# HSPROTO.net
KiCad netlist of a schematic drawn in EAGLE
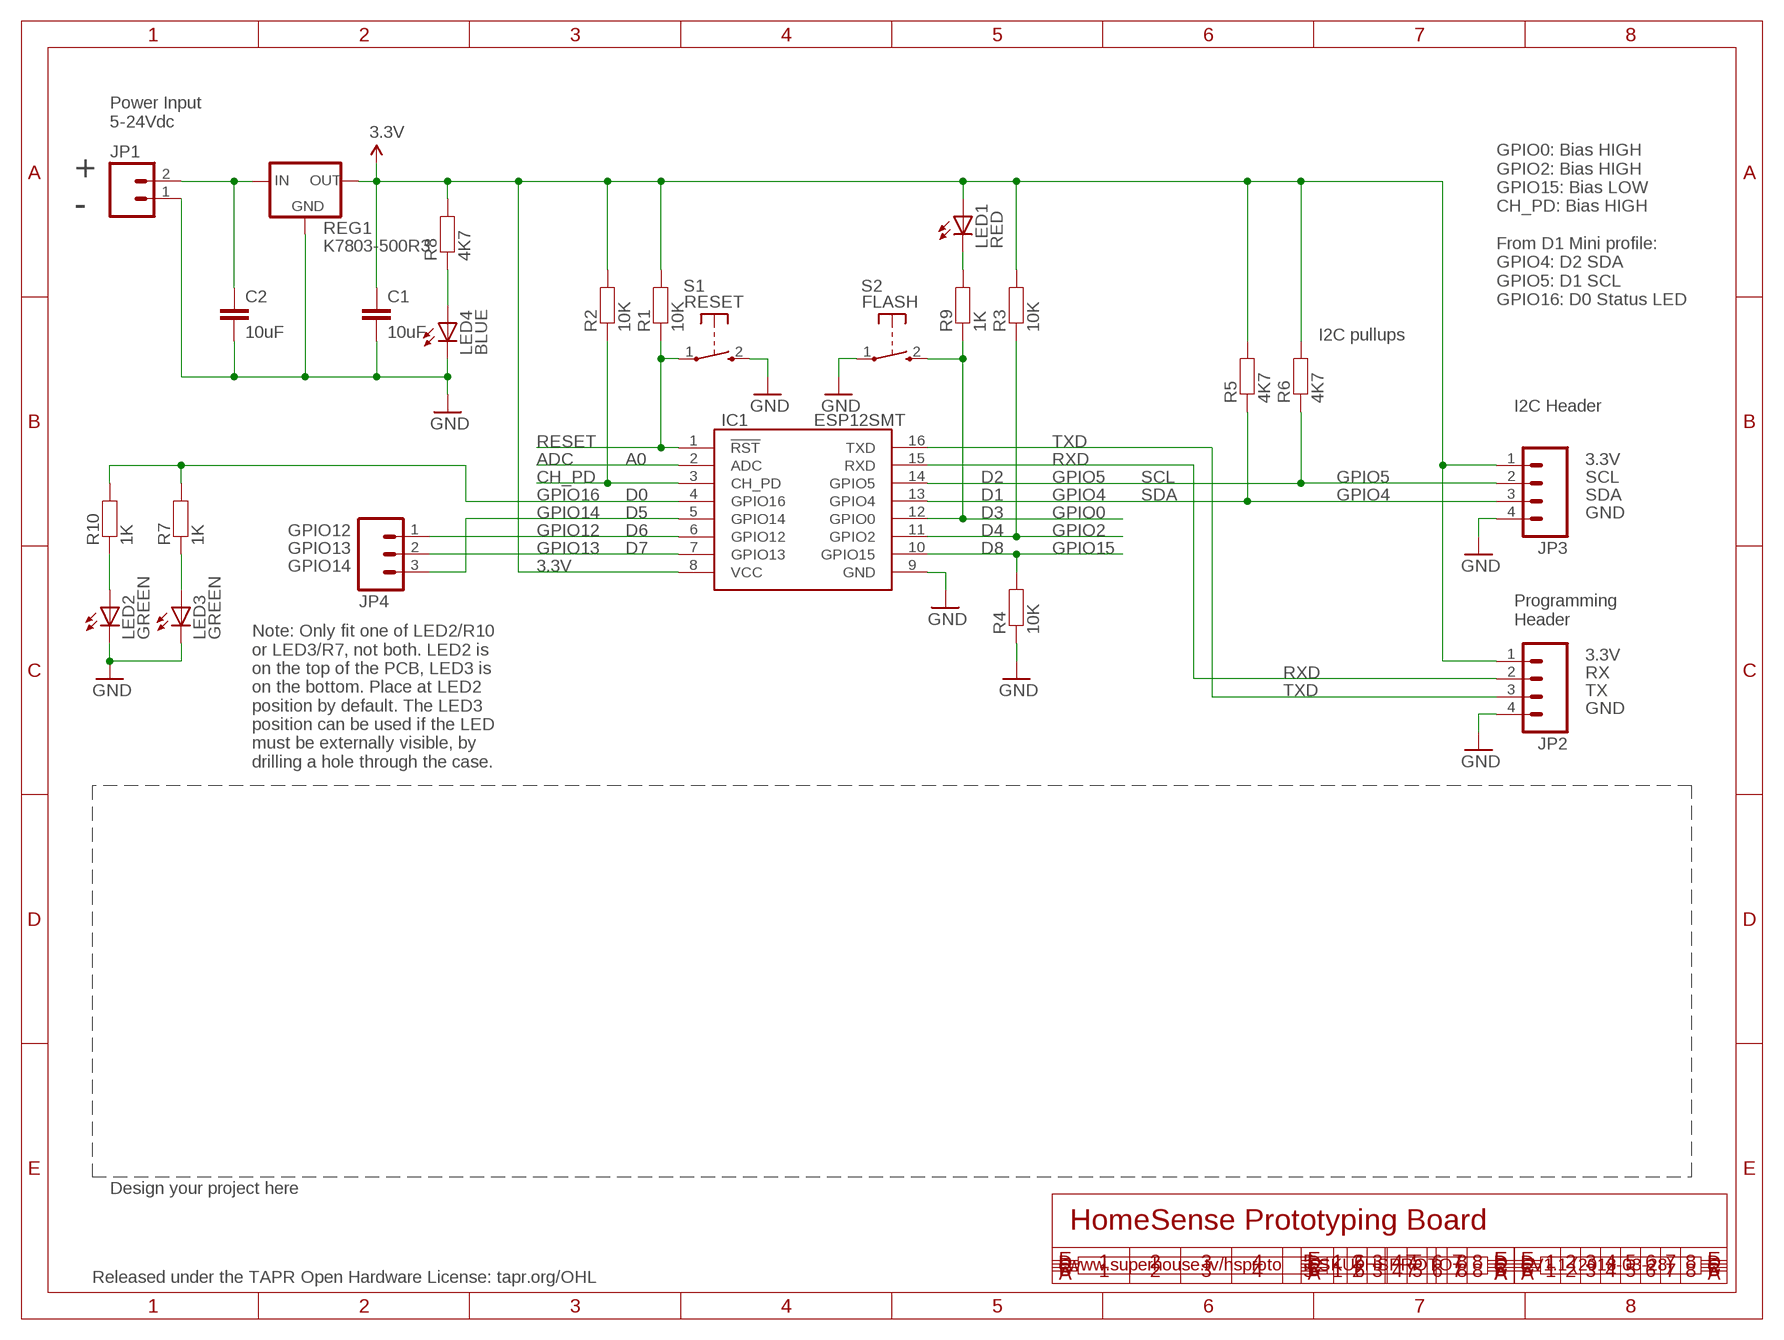
[diagram p0: schematic, sheet 1]

(export (version "E")
  (design (tool "Eeschema 10.0.6"))
  (components
    (comp (ref "C1")
      (value "10uF")
      (footprint "eagle-import:0805")
      (libsource (lib "eagle-import") (part "CAP0805"))
    )
    (comp (ref "C2")
      (value "10uF")
      (footprint "eagle-import:0805")
      (libsource (lib "eagle-import") (part "CAP0805"))
    )
    (comp (ref "IC1")
      (value "ESP12SMT")
      (footprint "eagle-import:ESP12")
      (libsource (lib "eagle-import") (part "ESP12SMT"))
    )
    (comp (ref "JP1")
      (value "M02PTH")
      (footprint "eagle-import:1X02")
      (libsource (lib "eagle-import") (part "M02PTH"))
    )
    (comp (ref "JP2")
      (value "M04PTH")
      (footprint "eagle-import:1X04")
      (libsource (lib "eagle-import") (part "M04PTH"))
    )
    (comp (ref "JP3")
      (value "M04PTH")
      (footprint "eagle-import:1X04")
      (libsource (lib "eagle-import") (part "M04PTH"))
    )
    (comp (ref "JP4")
      (value "M03PTH")
      (footprint "eagle-import:1X03")
      (libsource (lib "eagle-import") (part "M03PTH"))
    )
    (comp (ref "LED1")
      (value "RED")
      (footprint "eagle-import:LED-0603")
      (libsource (lib "eagle-import") (part "LED0603"))
    )
    (comp (ref "LED2")
      (value "GREEN")
      (footprint "eagle-import:LED-0603")
      (libsource (lib "eagle-import") (part "LED0603"))
    )
    (comp (ref "LED3")
      (value "GREEN")
      (footprint "eagle-import:LED-0603")
      (libsource (lib "eagle-import") (part "LED0603"))
    )
    (comp (ref "LED4")
      (value "BLUE")
      (footprint "eagle-import:LED-0603")
      (libsource (lib "eagle-import") (part "LED0603"))
    )
    (comp (ref "R1")
      (value "10K")
      (footprint "eagle-import:0603")
      (libsource (lib "eagle-import") (part "RESISTOR0603"))
    )
    (comp (ref "R2")
      (value "10K")
      (footprint "eagle-import:0603")
      (libsource (lib "eagle-import") (part "RESISTOR0603"))
    )
    (comp (ref "R3")
      (value "10K")
      (footprint "eagle-import:0603")
      (libsource (lib "eagle-import") (part "RESISTOR0603"))
    )
    (comp (ref "R4")
      (value "10K")
      (footprint "eagle-import:0603")
      (libsource (lib "eagle-import") (part "RESISTOR0603"))
    )
    (comp (ref "R5")
      (value "4K7")
      (footprint "eagle-import:0603")
      (libsource (lib "eagle-import") (part "RESISTOR0603"))
    )
    (comp (ref "R6")
      (value "4K7")
      (footprint "eagle-import:0603")
      (libsource (lib "eagle-import") (part "RESISTOR0603"))
    )
    (comp (ref "R7")
      (value "1K")
      (footprint "eagle-import:0603")
      (libsource (lib "eagle-import") (part "RESISTOR0603"))
    )
    (comp (ref "R8")
      (value "4K7")
      (footprint "eagle-import:0603")
      (libsource (lib "eagle-import") (part "RESISTOR0603"))
    )
    (comp (ref "R9")
      (value "1K")
      (footprint "eagle-import:0603")
      (libsource (lib "eagle-import") (part "RESISTOR0603"))
    )
    (comp (ref "R10")
      (value "1K")
      (footprint "eagle-import:0603")
      (libsource (lib "eagle-import") (part "RESISTOR0603"))
    )
    (comp (ref "REG1")
      (value "K7803-500R3")
      (footprint "eagle-import:K78XX-500R3")
      (libsource (lib "eagle-import") (part "K78XX-500R3"))
    )
    (comp (ref "S1")
      (value "RESET")
      (footprint "eagle-import:TACTILE_SWITCH_SMD_2PIN_TINY")
      (libsource (lib "eagle-import") (part "TAC_SWITCH_2PINSMT"))
    )
    (comp (ref "S2")
      (value "FLASH")
      (footprint "eagle-import:TACTILE_SWITCH_SMD_2PIN_TINY")
      (libsource (lib "eagle-import") (part "TAC_SWITCH_2PINSMT"))
    )
  )
  (nets
    (net (code "1") (name "/ADC") (class "Default")
      (node (ref "IC1") (pin "2") (pinfunction "ADC_2") (pintype "input"))
    )
    (net (code "2") (name "/CH_PD") (class "Default")
      (node (ref "IC1") (pin "3") (pinfunction "CH_PD_3") (pintype "input"))
      (node (ref "R2") (pin "1") (pinfunction "1_1") (pintype "passive"))
    )
    (net (code "3") (name "/GPIO0") (class "Default")
      (node (ref "IC1") (pin "12") (pinfunction "GPIO0_12") (pintype "bidirectional"))
      (node (ref "R9") (pin "1") (pinfunction "1_1") (pintype "passive"))
      (node (ref "S2") (pin "2") (pinfunction "S_2") (pintype "passive"))
    )
    (net (code "4") (name "/GPIO2") (class "Default")
      (node (ref "IC1") (pin "11") (pinfunction "GPIO2_11") (pintype "bidirectional"))
      (node (ref "R3") (pin "1") (pinfunction "1_1") (pintype "passive"))
    )
    (net (code "5") (name "/GPIO4") (class "Default")
      (node (ref "IC1") (pin "13") (pinfunction "GPIO4_13") (pintype "bidirectional"))
      (node (ref "JP3") (pin "3") (pinfunction "3_3") (pintype "passive"))
      (node (ref "R5") (pin "1") (pinfunction "1_1") (pintype "passive"))
    )
    (net (code "6") (name "/GPIO5") (class "Default")
      (node (ref "IC1") (pin "14") (pinfunction "GPIO5_14") (pintype "bidirectional"))
      (node (ref "JP3") (pin "2") (pinfunction "2_2") (pintype "passive"))
      (node (ref "R6") (pin "1") (pinfunction "1_1") (pintype "passive"))
    )
    (net (code "7") (name "/GPIO12") (class "Default")
      (node (ref "IC1") (pin "6") (pinfunction "GPIO12_6") (pintype "bidirectional"))
      (node (ref "JP4") (pin "1") (pinfunction "1_1") (pintype "passive"))
    )
    (net (code "8") (name "/GPIO13") (class "Default")
      (node (ref "IC1") (pin "7") (pinfunction "GPIO13_7") (pintype "bidirectional"))
      (node (ref "JP4") (pin "2") (pinfunction "2_2") (pintype "passive"))
    )
    (net (code "9") (name "/GPIO14") (class "Default")
      (node (ref "IC1") (pin "5") (pinfunction "GPIO14_5") (pintype "bidirectional"))
      (node (ref "JP4") (pin "3") (pinfunction "3_3") (pintype "passive"))
    )
    (net (code "10") (name "/GPIO15") (class "Default")
      (node (ref "IC1") (pin "10") (pinfunction "GPIO15_10") (pintype "bidirectional"))
      (node (ref "R4") (pin "2") (pinfunction "2_2") (pintype "passive"))
    )
    (net (code "11") (name "/GPIO16") (class "Default")
      (node (ref "IC1") (pin "4") (pinfunction "GPIO16_4") (pintype "bidirectional"))
      (node (ref "R10") (pin "2") (pinfunction "2_2") (pintype "passive"))
      (node (ref "R7") (pin "2") (pinfunction "2_2") (pintype "passive"))
    )
    (net (code "12") (name "/RESET") (class "Default")
      (node (ref "IC1") (pin "1") (pinfunction "~{RST}_1") (pintype "bidirectional"))
      (node (ref "R1") (pin "1") (pinfunction "1_1") (pintype "passive"))
      (node (ref "S1") (pin "1") (pinfunction "P_1") (pintype "passive"))
    )
    (net (code "13") (name "/RXD") (class "Default")
      (node (ref "IC1") (pin "15") (pinfunction "RXD_15") (pintype "input"))
      (node (ref "JP2") (pin "2") (pinfunction "2_2") (pintype "passive"))
    )
    (net (code "14") (name "/TXD") (class "Default")
      (node (ref "IC1") (pin "16") (pinfunction "TXD_16") (pintype "output"))
      (node (ref "JP2") (pin "3") (pinfunction "3_3") (pintype "passive"))
    )
    (net (code "15") (name "3.3V") (class "Default")
      (node (ref "C1") (pin "1") (pinfunction "1_1") (pintype "passive"))
      (node (ref "IC1") (pin "8") (pinfunction "VCC_8") (pintype "power_in"))
      (node (ref "JP2") (pin "1") (pinfunction "1_1") (pintype "passive"))
      (node (ref "JP3") (pin "1") (pinfunction "1_1") (pintype "passive"))
      (node (ref "LED1") (pin "A") (pinfunction "A_A") (pintype "passive"))
      (node (ref "R1") (pin "2") (pinfunction "2_2") (pintype "passive"))
      (node (ref "R2") (pin "2") (pinfunction "2_2") (pintype "passive"))
      (node (ref "R3") (pin "2") (pinfunction "2_2") (pintype "passive"))
      (node (ref "R5") (pin "2") (pinfunction "2_2") (pintype "passive"))
      (node (ref "R6") (pin "2") (pinfunction "2_2") (pintype "passive"))
      (node (ref "R8") (pin "2") (pinfunction "2_2") (pintype "passive"))
      (node (ref "REG1") (pin "3") (pinfunction "OUT_3") (pintype "output"))
    )
    (net (code "16") (name "GND") (class "Default")
      (node (ref "C1") (pin "2") (pinfunction "2_2") (pintype "passive"))
      (node (ref "C2") (pin "2") (pinfunction "2_2") (pintype "passive"))
      (node (ref "IC1") (pin "9") (pinfunction "GND_9") (pintype "power_in"))
      (node (ref "JP1") (pin "1") (pinfunction "1_1") (pintype "passive"))
      (node (ref "JP2") (pin "4") (pinfunction "4_4") (pintype "passive"))
      (node (ref "JP3") (pin "4") (pinfunction "4_4") (pintype "passive"))
      (node (ref "LED2") (pin "C") (pinfunction "C_C") (pintype "passive"))
      (node (ref "LED3") (pin "C") (pinfunction "C_C") (pintype "passive"))
      (node (ref "LED4") (pin "C") (pinfunction "C_C") (pintype "passive"))
      (node (ref "R4") (pin "1") (pinfunction "1_1") (pintype "passive"))
      (node (ref "REG1") (pin "2") (pinfunction "GND_2") (pintype "input"))
      (node (ref "S1") (pin "2") (pinfunction "S_2") (pintype "passive"))
      (node (ref "S2") (pin "1") (pinfunction "P_1") (pintype "passive"))
    )
    (net (code "17") (name "Net-(LED1-PadC)") (class "Default")
      (node (ref "LED1") (pin "C") (pinfunction "C_C") (pintype "passive"))
      (node (ref "R9") (pin "2") (pinfunction "2_2") (pintype "passive"))
    )
    (net (code "18") (name "Net-(LED2-PadA)") (class "Default")
      (node (ref "LED2") (pin "A") (pinfunction "A_A") (pintype "passive"))
      (node (ref "R10") (pin "1") (pinfunction "1_1") (pintype "passive"))
    )
    (net (code "19") (name "Net-(LED3-PadA)") (class "Default")
      (node (ref "LED3") (pin "A") (pinfunction "A_A") (pintype "passive"))
      (node (ref "R7") (pin "1") (pinfunction "1_1") (pintype "passive"))
    )
    (net (code "20") (name "Net-(LED4-PadA)") (class "Default")
      (node (ref "LED4") (pin "A") (pinfunction "A_A") (pintype "passive"))
      (node (ref "R8") (pin "1") (pinfunction "1_1") (pintype "passive"))
    )
    (net (code "21") (name "Net-(REG1-IN)") (class "Default")
      (node (ref "C2") (pin "1") (pinfunction "1_1") (pintype "passive"))
      (node (ref "JP1") (pin "2") (pinfunction "2_2") (pintype "passive"))
      (node (ref "REG1") (pin "1") (pinfunction "IN_1") (pintype "input"))
    )
  )
)
